# BLL-EBOOK-3506B.net
KiCad netlist of a schematic drawn in EAGLE
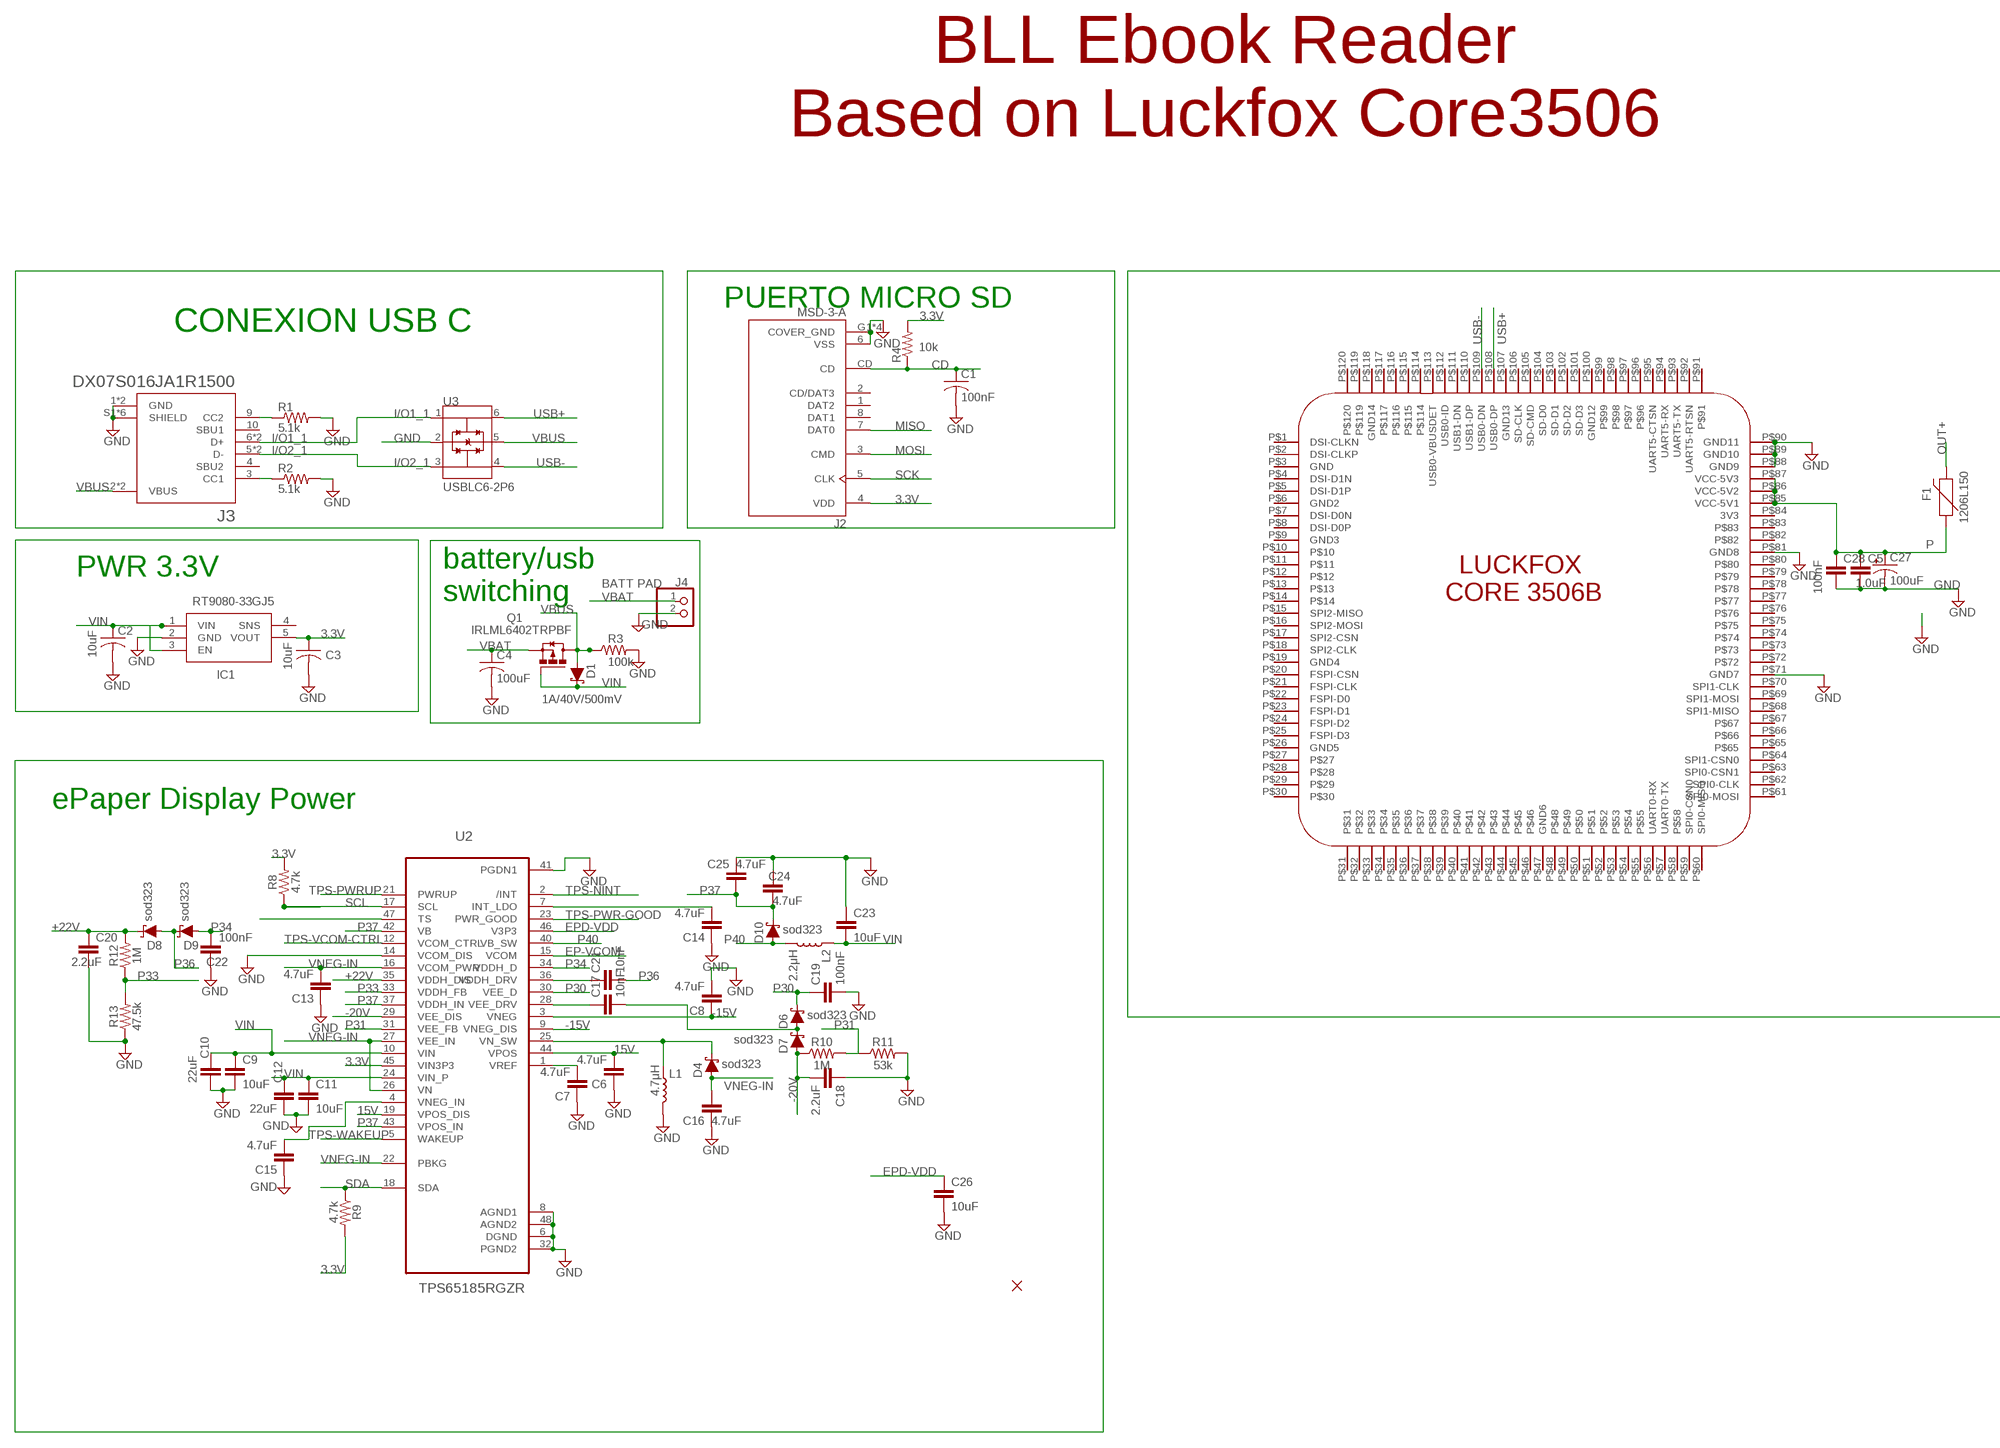
[diagram p0: schematic, sheet 1, part 1 of 2]
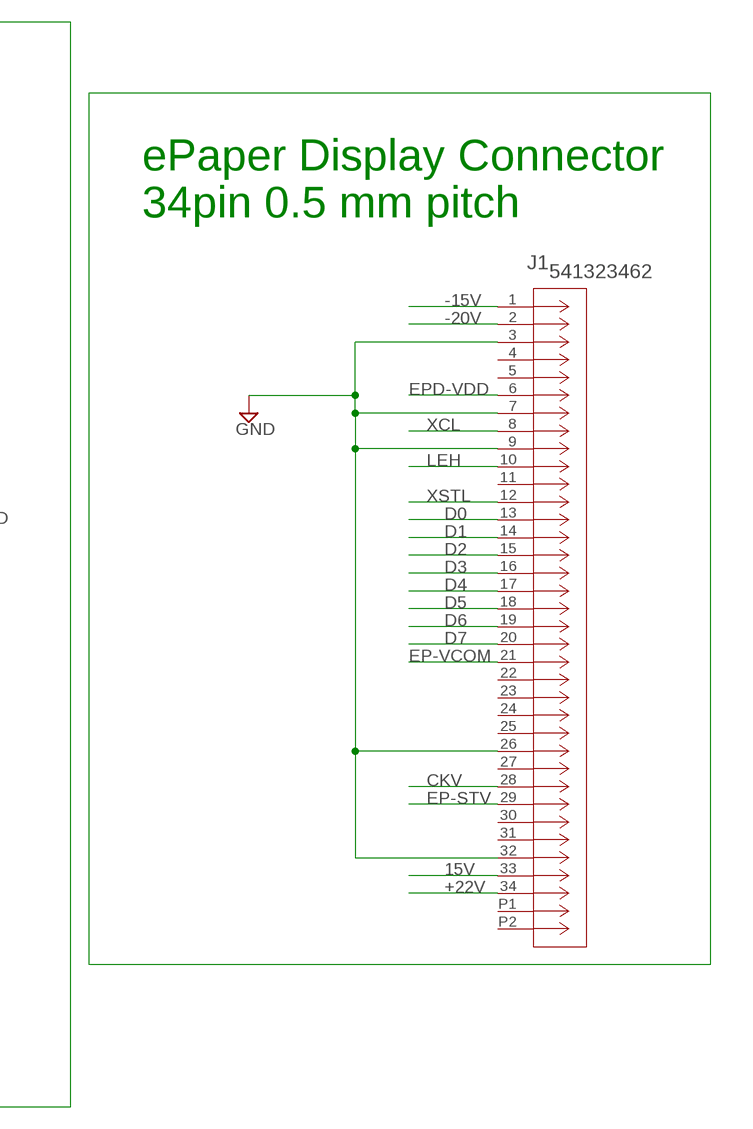
[diagram p1: schematic, sheet 1, part 2 of 2]

(export (version "E")
  (design (tool "Eeschema 10.0.6"))
  (components
    (comp (ref "C1")
      (value "100nF")
      (footprint "eagle-import:C0603")
      (libsource (lib "eagle-import") (part "C-USC0603"))
    )
    (comp (ref "C2")
      (value "10uF")
      (footprint "eagle-import:C0603")
      (libsource (lib "eagle-import") (part "C-USC0603"))
    )
    (comp (ref "C3")
      (value "10uF")
      (footprint "eagle-import:C0603")
      (libsource (lib "eagle-import") (part "C-USC0603"))
    )
    (comp (ref "C4")
      (value "100uF")
      (footprint "eagle-import:C0603")
      (libsource (lib "eagle-import") (part "C-USC0603"))
    )
    (comp (ref "C5")
      (value "1.0uF")
      (footprint "eagle-import:0603")
      (libsource (lib "eagle-import") (part "1.0UF-0603-16V-10%-X7R"))
    )
    (comp (ref "C6")
      (value "4.7uF")
      (footprint "eagle-import:0603")
      (libsource (lib "eagle-import") (part "4.7UF-0603-35V-(20%)"))
    )
    (comp (ref "C7")
      (value "4.7uF")
      (footprint "eagle-import:0603")
      (libsource (lib "eagle-import") (part "4.7UF-0603-35V-(20%)"))
    )
    (comp (ref "C8")
      (value "4.7uF")
      (footprint "eagle-import:0603")
      (libsource (lib "eagle-import") (part "4.7UF-0603-35V-(20%)"))
    )
    (comp (ref "C9")
      (value "10uF")
      (footprint "eagle-import:0805")
      (libsource (lib "eagle-import") (part "10UF-0805-10V-10%"))
    )
    (comp (ref "C10")
      (value "22uF")
      (footprint "eagle-import:0805")
      (libsource (lib "eagle-import") (part "22UF-0805-16V-20%"))
    )
    (comp (ref "C11")
      (value "10uF")
      (footprint "eagle-import:0805")
      (libsource (lib "eagle-import") (part "10UF-0805-10V-10%"))
    )
    (comp (ref "C12")
      (value "22uF")
      (footprint "eagle-import:0805")
      (libsource (lib "eagle-import") (part "22UF-0805-16V-20%"))
    )
    (comp (ref "C13")
      (value "4.7uF")
      (footprint "eagle-import:0603")
      (libsource (lib "eagle-import") (part "4.7UF-0603-35V-(20%)"))
    )
    (comp (ref "C14")
      (value "4.7uF")
      (footprint "eagle-import:0603")
      (libsource (lib "eagle-import") (part "4.7UF-0603-35V-(20%)"))
    )
    (comp (ref "C15")
      (value "4.7uF")
      (footprint "eagle-import:0603")
      (libsource (lib "eagle-import") (part "4.7UF-0603-35V-(20%)"))
    )
    (comp (ref "C16")
      (value "4.7uF")
      (footprint "eagle-import:0603")
      (libsource (lib "eagle-import") (part "4.7UF-0603-35V-(20%)"))
    )
    (comp (ref "C17")
      (value "10nF")
      (footprint "eagle-import:0603")
      (libsource (lib "eagle-import") (part "10NF-0603-50V-10%"))
    )
    (comp (ref "C18")
      (value "2.2uF")
      (footprint "eagle-import:1206")
      (libsource (lib "eagle-import") (part "2.2UF-1206-50V-10%"))
    )
    (comp (ref "C19")
      (value "100nF")
      (footprint "eagle-import:0603")
      (libsource (lib "eagle-import") (part "DNP-0603"))
    )
    (comp (ref "C20")
      (value "2.2uF")
      (footprint "eagle-import:1206")
      (libsource (lib "eagle-import") (part "2.2UF-1206-50V-10%"))
    )
    (comp (ref "C21")
      (value "10nF")
      (footprint "eagle-import:0603")
      (libsource (lib "eagle-import") (part "10NF-0603-50V-10%"))
    )
    (comp (ref "C22")
      (value "100nF")
      (footprint "eagle-import:0603")
      (libsource (lib "eagle-import") (part "DNP-0603"))
    )
    (comp (ref "C23")
      (value "10uF")
      (footprint "eagle-import:0805")
      (libsource (lib "eagle-import") (part "10UF-0805-10V-10%"))
    )
    (comp (ref "C24")
      (value "4.7uF")
      (footprint "eagle-import:0603")
      (libsource (lib "eagle-import") (part "4.7UF-0603-35V-(20%)"))
    )
    (comp (ref "C25")
      (value "4.7uF")
      (footprint "eagle-import:0603")
      (libsource (lib "eagle-import") (part "4.7UF-0603-35V-(20%)"))
    )
    (comp (ref "C26")
      (value "10uF")
      (footprint "eagle-import:0805")
      (libsource (lib "eagle-import") (part "10UF-0805-10V-10%"))
    )
    (comp (ref "C27")
      (value "100uF")
      (footprint "eagle-import:EIA3528")
      (libsource (lib "eagle-import") (part "100UF-POLAR-EIA3528-10V-20%(TANT)"))
    )
    (comp (ref "C28")
      (value "100nF")
      (footprint "eagle-import:0805")
      (libsource (lib "eagle-import") (part "CAP-0805"))
    )
    (comp (ref "D1")
      (value "1A/40V/500mV")
      (footprint "eagle-import:SMA-DIODE")
      (libsource (lib "eagle-import") (part "DIODE-SCHOTTKY-SS14"))
    )
    (comp (ref "D4")
      (value "sod323")
      (footprint "eagle-import:SOD-323")
      (libsource (lib "eagle-import") (part "DIODE-SCHOTTKY-PMEG4005EJ"))
    )
    (comp (ref "D6")
      (value "sod323")
      (footprint "eagle-import:SOD-323")
      (libsource (lib "eagle-import") (part "DIODE-SCHOTTKY-PMEG4005EJ"))
    )
    (comp (ref "D7")
      (value "sod323")
      (footprint "eagle-import:SOD-323")
      (libsource (lib "eagle-import") (part "DIODE-SCHOTTKY-PMEG4005EJ"))
    )
    (comp (ref "D8")
      (value "sod323")
      (footprint "eagle-import:SOD-323")
      (libsource (lib "eagle-import") (part "DIODE-SCHOTTKY-PMEG4005EJ"))
    )
    (comp (ref "D9")
      (value "sod323")
      (footprint "eagle-import:SOD-323")
      (libsource (lib "eagle-import") (part "DIODE-SCHOTTKY-PMEG4005EJ"))
    )
    (comp (ref "D10")
      (value "sod323")
      (footprint "eagle-import:SOD-323")
      (libsource (lib "eagle-import") (part "DIODE-SCHOTTKY-PMEG4005EJ"))
    )
    (comp (ref "F1")
      (value "1206L150")
      (footprint "eagle-import:1206")
      (libsource (lib "eagle-import") (part "PPTC_6V500MA-2"))
    )
    (comp (ref "IC1")
      (value "RT9080-33GJ5")
      (footprint "eagle-import:SOT94P280X100-5N")
      (fields (field (name "MF") "Richtek USA"))
      (libsource (lib "eagle-import") (part "RT9080-33GJ5"))
    )
    (comp (ref "J1")
      (value "541323462")
      (footprint "eagle-import:CON_541323462_MOL")
      (fields (field (name "MF") "Molex"))
      (libsource (lib "eagle-import") (part "541323462"))
    )
    (comp (ref "J2")
      (value "MSD-3-A")
      (footprint "eagle-import:CUI_MSD-3-A")
      (fields (field (name "MF") "Same Sky"))
      (libsource (lib "eagle-import") (part "MSD-3-A"))
    )
    (comp (ref "J3")
      (value "DX07S016JA1R1500")
      (footprint "eagle-import:JAE_DX07S016JA1R1500")
      (fields (field (name "MF") "JAE Electronics"))
      (libsource (lib "eagle-import") (part "DX07S016JA1R1500"))
    )
    (comp (ref "J4")
      (value "BATT PAD")
      (footprint "eagle-import:1X02_90")
      (libsource (lib "eagle-import") (part "PINHD-1X2/90"))
    )
    (comp (ref "L1")
      (value "4.7μH")
      (footprint "eagle-import:1008(2520)")
      (libsource (lib "eagle-import") (part "4.7μH_SHIELDED_INDUCTOR"))
    )
    (comp (ref "L2")
      (value "2.2μH")
      (footprint "eagle-import:0806")
      (libsource (lib "eagle-import") (part "2.2μH_SHIELDED_INDUCTOR"))
    )
    (comp (ref "Q1")
      (value "IRLML6402TRPBF")
      (footprint "eagle-import:SOT23")
      (fields (field (name "MF") "Infineon Technologies") (field (name "MP") "IRLML6402"))
      (libsource (lib "eagle-import") (part "IRLML6402TRPBF"))
    )
    (comp (ref "R1")
      (value "5.1k")
      (footprint "eagle-import:M0805")
      (libsource (lib "eagle-import") (part "R-US_M0805"))
    )
    (comp (ref "R2")
      (value "5.1k")
      (footprint "eagle-import:M0805")
      (libsource (lib "eagle-import") (part "R-US_M0805"))
    )
    (comp (ref "R3")
      (value "100k")
      (footprint "eagle-import:R0603")
      (libsource (lib "eagle-import") (part "R-US_R0603"))
    )
    (comp (ref "R4")
      (value "10k")
      (footprint "eagle-import:M0805")
      (libsource (lib "eagle-import") (part "R-US_M0805"))
    )
    (comp (ref "R8")
      (value "4.7k")
      (footprint "eagle-import:0603")
      (libsource (lib "eagle-import") (part "4.7KOHM-0603-1/10W-1%"))
    )
    (comp (ref "R9")
      (value "4.7k")
      (footprint "eagle-import:0603")
      (libsource (lib "eagle-import") (part "4.7KOHM-0603-1/10W-1%"))
    )
    (comp (ref "R10")
      (value "1M")
      (footprint "eagle-import:0603")
      (libsource (lib "eagle-import") (part "1MOHM-0603-1/4W-5%"))
    )
    (comp (ref "R11")
      (value "53k")
      (footprint "eagle-import:0805")
      (libsource (lib "eagle-import") (part "RESISTOR0805"))
    )
    (comp (ref "R12")
      (value "1M")
      (footprint "eagle-import:0603")
      (libsource (lib "eagle-import") (part "1MOHM-0603-1/4W-5%"))
    )
    (comp (ref "R13")
      (value "47.5k")
      (footprint "eagle-import:0805")
      (libsource (lib "eagle-import") (part "RESISTOR0805"))
    )
    (comp (ref "U$1")
      (value "LUCKFOX_CORE3506")
      (footprint "eagle-import:CORE3506")
      (libsource (lib "eagle-import") (part "LUCKFOX_CORE3506"))
    )
    (comp (ref "U2")
      (value "TPS65185RGZR")
      (footprint "eagle-import:QFN50P700X700X100-49N")
      (fields (field (name "MF") "Texas Instruments"))
      (libsource (lib "eagle-import") (part "TPS65185RGZR"))
    )
    (comp (ref "U3")
      (value "USBLC6-2P6")
      (footprint "eagle-import:SOT50P160X60-6N")
      (fields (field (name "MF") "STMicroelectronics"))
      (libsource (lib "eagle-import") (part "USBLC6-2P6"))
    )
  )
  (nets
    (net (code "1") (name "/+22V") (class "Default")
      (node (ref "C20") (pin "1") (pinfunction "1_1") (pintype "passive"))
      (node (ref "D8") (pin "C") (pinfunction "C_C") (pintype "passive"))
      (node (ref "J1") (pin "34") (pinfunction "34_34") (pintype "passive"))
      (node (ref "R12") (pin "2") (pinfunction "2_2") (pintype "passive"))
      (node (ref "U2") (pin "35") (pinfunction "VDDH_DIS_35") (pintype "input"))
    )
    (net (code "2") (name "/-15V") (class "Default")
      (node (ref "C8") (pin "1") (pinfunction "1_1") (pintype "passive"))
      (node (ref "J1") (pin "1") (pinfunction "1_1") (pintype "passive"))
      (node (ref "U2") (pin "3") (pinfunction "VNEG_3") (pintype "output"))
      (node (ref "U2") (pin "9") (pinfunction "VNEG_DIS_9") (pintype "output"))
    )
    (net (code "3") (name "/-20V") (class "Default")
      (node (ref "C18") (pin "2") (pinfunction "2_2") (pintype "passive"))
      (node (ref "D7") (pin "A") (pinfunction "A_A") (pintype "passive"))
      (node (ref "J1") (pin "2") (pinfunction "2_2") (pintype "passive"))
      (node (ref "R10") (pin "1") (pinfunction "1_1") (pintype "passive"))
      (node (ref "U2") (pin "29") (pinfunction "VEE_DIS_29") (pintype "input"))
    )
    (net (code "4") (name "/3.3V") (class "Default")
      (node (ref "C3") (pin "1") (pinfunction "1_1") (pintype "passive"))
      (node (ref "IC1") (pin "5") (pinfunction "VOUT_5") (pintype "bidirectional"))
      (node (ref "J2") (pin "4") (pinfunction "VDD_4") (pintype "power_in"))
      (node (ref "R4") (pin "2") (pinfunction "2_2") (pintype "passive"))
      (node (ref "R8") (pin "2") (pinfunction "2_2") (pintype "passive"))
      (node (ref "R9") (pin "2") (pinfunction "2_2") (pintype "passive"))
      (node (ref "U2") (pin "45") (pinfunction "VIN3P3_45") (pintype "input"))
    )
    (net (code "5") (name "/15V") (class "Default")
      (node (ref "C6") (pin "2") (pinfunction "2_2") (pintype "passive"))
      (node (ref "J1") (pin "33") (pinfunction "33_33") (pintype "passive"))
      (node (ref "U2") (pin "19") (pinfunction "VPOS_DIS_19") (pintype "input"))
      (node (ref "U2") (pin "44") (pinfunction "VPOS_44") (pintype "output"))
    )
    (net (code "6") (name "/CD") (class "Default")
      (node (ref "C1") (pin "1") (pinfunction "1_1") (pintype "passive"))
      (node (ref "J2") (pin "CD") (pinfunction "CD_CD") (pintype "passive"))
      (node (ref "R4") (pin "1") (pinfunction "1_1") (pintype "passive"))
    )
    (net (code "7") (name "/CKV") (class "Default")
      (node (ref "J1") (pin "28") (pinfunction "28_28") (pintype "passive"))
    )
    (net (code "8") (name "/D0") (class "Default")
      (node (ref "J1") (pin "13") (pinfunction "13_13") (pintype "passive"))
    )
    (net (code "9") (name "/D1") (class "Default")
      (node (ref "J1") (pin "14") (pinfunction "14_14") (pintype "passive"))
    )
    (net (code "10") (name "/D2") (class "Default")
      (node (ref "J1") (pin "15") (pinfunction "15_15") (pintype "passive"))
    )
    (net (code "11") (name "/D3") (class "Default")
      (node (ref "J1") (pin "16") (pinfunction "16_16") (pintype "passive"))
    )
    (net (code "12") (name "/D4") (class "Default")
      (node (ref "J1") (pin "17") (pinfunction "17_17") (pintype "passive"))
    )
    (net (code "13") (name "/D5") (class "Default")
      (node (ref "J1") (pin "18") (pinfunction "18_18") (pintype "passive"))
    )
    (net (code "14") (name "/D6") (class "Default")
      (node (ref "J1") (pin "19") (pinfunction "19_19") (pintype "passive"))
    )
    (net (code "15") (name "/D7") (class "Default")
      (node (ref "J1") (pin "20") (pinfunction "20_20") (pintype "passive"))
    )
    (net (code "16") (name "/EP-STV") (class "Default")
      (node (ref "J1") (pin "29") (pinfunction "29_29") (pintype "passive"))
    )
    (net (code "17") (name "/EP-VCOM") (class "Default")
      (node (ref "J1") (pin "21") (pinfunction "21_21") (pintype "passive"))
      (node (ref "U2") (pin "15") (pinfunction "VCOM_15") (pintype "output"))
    )
    (net (code "18") (name "/EPD-VDD") (class "Default")
      (node (ref "C26") (pin "1") (pinfunction "1_1") (pintype "passive"))
      (node (ref "J1") (pin "6") (pinfunction "6_6") (pintype "passive"))
      (node (ref "U2") (pin "46") (pinfunction "V3P3_46") (pintype "output"))
    )
    (net (code "19") (name "/I{slash}O1_1") (class "Default")
      (node (ref "J3") (pin "6") (pinfunction "D+_6") (pintype "passive"))
      (node (ref "J3") (pin "7") (pinfunction "D+_7") (pintype "passive"))
      (node (ref "U3") (pin "1") (pinfunction "I/O1_1_1") (pintype "bidirectional"))
    )
    (net (code "20") (name "/I{slash}O2_1") (class "Default")
      (node (ref "J3") (pin "5") (pinfunction "D-_5") (pintype "passive"))
      (node (ref "J3") (pin "8") (pinfunction "D-_8") (pintype "passive"))
      (node (ref "U3") (pin "3") (pinfunction "I/O2_1_3") (pintype "bidirectional"))
    )
    (net (code "21") (name "/LEH") (class "Default")
      (node (ref "J1") (pin "10") (pinfunction "10_10") (pintype "passive"))
    )
    (net (code "22") (name "/MISO") (class "Default")
      (node (ref "J2") (pin "7") (pinfunction "DAT0_7") (pintype "bidirectional"))
    )
    (net (code "23") (name "/MOSI") (class "Default")
      (node (ref "J2") (pin "3") (pinfunction "CMD_3") (pintype "bidirectional"))
    )
    (net (code "24") (name "/OUT+") (class "Default")
      (node (ref "F1") (pin "2") (pinfunction "2_2") (pintype "bidirectional"))
    )
    (net (code "25") (name "/P") (class "Default")
      (node (ref "C27") (pin "A") (pinfunction "+_A") (pintype "passive"))
      (node (ref "C28") (pin "1") (pinfunction "1_1") (pintype "passive"))
      (node (ref "C5") (pin "1") (pinfunction "1_1") (pintype "passive"))
      (node (ref "F1") (pin "1") (pinfunction "1_1") (pintype "bidirectional"))
      (node (ref "U$1") (pin "P$85") (pinfunction "VCC-5V1_P$85") (pintype "bidirectional"))
      (node (ref "U$1") (pin "P$86") (pinfunction "VCC-5V2_P$86") (pintype "bidirectional"))
      (node (ref "U$1") (pin "P$87") (pinfunction "VCC-5V3_P$87") (pintype "bidirectional"))
    )
    (net (code "26") (name "/P30") (class "Default")
      (node (ref "C19") (pin "1") (pinfunction "1_1") (pintype "passive"))
      (node (ref "D6") (pin "C") (pinfunction "C_C") (pintype "passive"))
      (node (ref "U2") (pin "30") (pinfunction "VEE_D_30") (pintype "output"))
    )
    (net (code "27") (name "/P31") (class "Default")
      (node (ref "R10") (pin "2") (pinfunction "2_2") (pintype "passive"))
      (node (ref "R11") (pin "1") (pinfunction "1_1") (pintype "passive"))
      (node (ref "U2") (pin "31") (pinfunction "VEE_FB_31") (pintype "input"))
    )
    (net (code "28") (name "/P33") (class "Default")
      (node (ref "R12") (pin "1") (pinfunction "1_1") (pintype "passive"))
      (node (ref "R13") (pin "2") (pinfunction "2_2") (pintype "passive"))
      (node (ref "U2") (pin "33") (pinfunction "VDDH_FB_33") (pintype "input"))
    )
    (net (code "29") (name "/P34") (class "Default")
      (node (ref "C22") (pin "2") (pinfunction "2_2") (pintype "passive"))
      (node (ref "D9") (pin "A") (pinfunction "A_A") (pintype "passive"))
      (node (ref "U2") (pin "34") (pinfunction "VDDH_D_34") (pintype "output"))
    )
    (net (code "30") (name "/P36") (class "Default")
      (node (ref "C21") (pin "2") (pinfunction "2_2") (pintype "passive"))
      (node (ref "D8") (pin "A") (pinfunction "A_A") (pintype "passive"))
      (node (ref "D9") (pin "C") (pinfunction "C_C") (pintype "passive"))
    )
    (net (code "31") (name "/P37") (class "Default")
      (node (ref "C24") (pin "1") (pinfunction "1_1") (pintype "passive"))
      (node (ref "C25") (pin "1") (pinfunction "1_1") (pintype "passive"))
      (node (ref "D10") (pin "C") (pinfunction "C_C") (pintype "passive"))
      (node (ref "U2") (pin "37") (pinfunction "VDDH_IN_37") (pintype "input"))
      (node (ref "U2") (pin "42") (pinfunction "VB_42") (pintype "input"))
      (node (ref "U2") (pin "43") (pinfunction "VPOS_IN_43") (pintype "input"))
    )
    (net (code "32") (name "/P40") (class "Default")
      (node (ref "D10") (pin "A") (pinfunction "A_A") (pintype "passive"))
      (node (ref "L2") (pin "2") (pinfunction "2_2") (pintype "passive"))
      (node (ref "U2") (pin "40") (pinfunction "VB_SW_40") (pintype "output"))
    )
    (net (code "33") (name "/SCK") (class "Default")
      (node (ref "J2") (pin "5") (pinfunction "CLK_5") (pintype "input"))
    )
    (net (code "34") (name "/SCL") (class "Default")
      (node (ref "R8") (pin "1") (pinfunction "1_1") (pintype "passive"))
      (node (ref "U2") (pin "17") (pinfunction "SCL_17") (pintype "input"))
    )
    (net (code "35") (name "/SDA") (class "Default")
      (node (ref "R9") (pin "1") (pinfunction "1_1") (pintype "passive"))
      (node (ref "U2") (pin "18") (pinfunction "SDA_18") (pintype "bidirectional"))
    )
    (net (code "36") (name "/TPS-NINT") (class "Default")
      (node (ref "U2") (pin "2") (pinfunction "/INT_2") (pintype "output"))
    )
    (net (code "37") (name "/TPS-PWR-GOOD") (class "Default")
      (node (ref "U2") (pin "23") (pinfunction "PWR_GOOD_23") (pintype "output"))
    )
    (net (code "38") (name "/TPS-PWRUP") (class "Default")
      (node (ref "U2") (pin "21") (pinfunction "PWRUP_21") (pintype "input"))
    )
    (net (code "39") (name "/TPS-VCOM-CTRL") (class "Default")
      (node (ref "U2") (pin "12") (pinfunction "VCOM_CTRL_12") (pintype "input"))
    )
    (net (code "40") (name "/TPS-WAKEUP") (class "Default")
      (node (ref "U2") (pin "5") (pinfunction "WAKEUP_5") (pintype "input"))
    )
    (net (code "41") (name "/USB+") (class "Default")
      (node (ref "U$1") (pin "P$108") (pinfunction "USB0-DP_P$108") (pintype "bidirectional"))
      (node (ref "U3") (pin "6") (pinfunction "I/O1_2_6") (pintype "bidirectional"))
    )
    (net (code "42") (name "/USB-") (class "Default")
      (node (ref "U$1") (pin "P$109") (pinfunction "USB0-DN_P$109") (pintype "bidirectional"))
      (node (ref "U3") (pin "4") (pinfunction "I/O2_2_4") (pintype "bidirectional"))
    )
    (net (code "43") (name "/VBAT") (class "Default")
      (node (ref "C4") (pin "1") (pinfunction "1_1") (pintype "passive"))
      (node (ref "J4") (pin "1") (pinfunction "1_1") (pintype "passive"))
      (node (ref "Q1") (pin "2") (pinfunction "S_2") (pintype "passive"))
    )
    (net (code "44") (name "/VBUS") (class "Default")
      (node (ref "D1") (pin "A") (pinfunction "A_A") (pintype "passive"))
      (node (ref "J3") (pin "11") (pinfunction "VBUS_11") (pintype "power_in"))
      (node (ref "J3") (pin "2") (pinfunction "VBUS_2") (pintype "power_in"))
      (node (ref "Q1") (pin "3") (pinfunction "D_3") (pintype "passive"))
      (node (ref "R3") (pin "1") (pinfunction "1_1") (pintype "passive"))
      (node (ref "U3") (pin "5") (pinfunction "VBUS_5") (pintype "power_in"))
    )
    (net (code "45") (name "/VIN") (class "Default")
      (node (ref "C10") (pin "1") (pinfunction "1_1") (pintype "passive"))
      (node (ref "C11") (pin "1") (pinfunction "1_1") (pintype "passive"))
      (node (ref "C12") (pin "1") (pinfunction "1_1") (pintype "passive"))
      (node (ref "C2") (pin "1") (pinfunction "1_1") (pintype "passive"))
      (node (ref "C23") (pin "2") (pinfunction "2_2") (pintype "passive"))
      (node (ref "C9") (pin "1") (pinfunction "1_1") (pintype "passive"))
      (node (ref "D1") (pin "C") (pinfunction "C_C") (pintype "passive"))
      (node (ref "IC1") (pin "1") (pinfunction "VIN_1") (pintype "bidirectional"))
      (node (ref "IC1") (pin "3") (pinfunction "EN_3") (pintype "bidirectional"))
      (node (ref "L2") (pin "1") (pinfunction "1_1") (pintype "passive"))
      (node (ref "Q1") (pin "1") (pinfunction "G_1") (pintype "passive"))
      (node (ref "U2") (pin "10") (pinfunction "VIN_10") (pintype "input"))
      (node (ref "U2") (pin "24") (pinfunction "VIN_P_24") (pintype "input"))
    )
    (net (code "46") (name "/VNEG-IN") (class "Default")
      (node (ref "C13") (pin "2") (pinfunction "2_2") (pintype "passive"))
      (node (ref "C16") (pin "2") (pinfunction "2_2") (pintype "passive"))
      (node (ref "D4") (pin "A") (pinfunction "A_A") (pintype "passive"))
      (node (ref "U2") (pin "16") (pinfunction "VCOM_PWR_16") (pintype "input"))
      (node (ref "U2") (pin "22") (pinfunction "PBKG_22") (pintype "bidirectional"))
      (node (ref "U2") (pin "26") (pinfunction "VN_26") (pintype "input"))
      (node (ref "U2") (pin "27") (pinfunction "VEE_IN_27") (pintype "input"))
    )
    (net (code "47") (name "/XCL") (class "Default")
      (node (ref "J1") (pin "8") (pinfunction "8_8") (pintype "passive"))
    )
    (net (code "48") (name "/XSTL") (class "Default")
      (node (ref "J1") (pin "12") (pinfunction "12_12") (pintype "passive"))
    )
    (net (code "49") (name "GND") (class "Default")
      (node (ref "C1") (pin "2") (pinfunction "2_2") (pintype "passive"))
      (node (ref "C10") (pin "2") (pinfunction "2_2") (pintype "passive"))
      (node (ref "C11") (pin "2") (pinfunction "2_2") (pintype "passive"))
      (node (ref "C12") (pin "2") (pinfunction "2_2") (pintype "passive"))
      (node (ref "C13") (pin "1") (pinfunction "1_1") (pintype "passive"))
      (node (ref "C14") (pin "1") (pinfunction "1_1") (pintype "passive"))
      (node (ref "C15") (pin "1") (pinfunction "1_1") (pintype "passive"))
      (node (ref "C16") (pin "1") (pinfunction "1_1") (pintype "passive"))
      (node (ref "C18") (pin "1") (pinfunction "1_1") (pintype "passive"))
      (node (ref "C19") (pin "2") (pinfunction "2_2") (pintype "passive"))
      (node (ref "C2") (pin "2") (pinfunction "2_2") (pintype "passive"))
      (node (ref "C20") (pin "2") (pinfunction "2_2") (pintype "passive"))
      (node (ref "C22") (pin "1") (pinfunction "1_1") (pintype "passive"))
      (node (ref "C23") (pin "1") (pinfunction "1_1") (pintype "passive"))
      (node (ref "C24") (pin "2") (pinfunction "2_2") (pintype "passive"))
      (node (ref "C25") (pin "2") (pinfunction "2_2") (pintype "passive"))
      (node (ref "C26") (pin "2") (pinfunction "2_2") (pintype "passive"))
      (node (ref "C27") (pin "C") (pinfunction "-_C") (pintype "passive"))
      (node (ref "C28") (pin "2") (pinfunction "2_2") (pintype "passive"))
      (node (ref "C3") (pin "2") (pinfunction "2_2") (pintype "passive"))
      (node (ref "C4") (pin "2") (pinfunction "2_2") (pintype "passive"))
      (node (ref "C5") (pin "2") (pinfunction "2_2") (pintype "passive"))
      (node (ref "C6") (pin "1") (pinfunction "1_1") (pintype "passive"))
      (node (ref "C7") (pin "1") (pinfunction "1_1") (pintype "passive"))
      (node (ref "C8") (pin "2") (pinfunction "2_2") (pintype "passive"))
      (node (ref "C9") (pin "2") (pinfunction "2_2") (pintype "passive"))
      (node (ref "IC1") (pin "2") (pinfunction "GND_2") (pintype "bidirectional"))
      (node (ref "J1") (pin "26") (pinfunction "26_26") (pintype "passive"))
      (node (ref "J1") (pin "3") (pinfunction "3_3") (pintype "passive"))
      (node (ref "J1") (pin "32") (pinfunction "32_32") (pintype "passive"))
      (node (ref "J1") (pin "7") (pinfunction "7_7") (pintype "passive"))
      (node (ref "J1") (pin "9") (pinfunction "9_9") (pintype "passive"))
      (node (ref "J2") (pin "6") (pinfunction "VSS_6") (pintype "power_in"))
      (node (ref "J2") (pin "G1") (pinfunction "COVER_GND_G1") (pintype "power_in"))
      (node (ref "J2") (pin "G2") (pinfunction "COVER_GND_G2") (pintype "power_in"))
      (node (ref "J2") (pin "G3") (pinfunction "COVER_GND_G3") (pintype "power_in"))
      (node (ref "J2") (pin "G4") (pinfunction "COVER_GND_G4") (pintype "power_in"))
      (node (ref "J3") (pin "1") (pinfunction "GND_1") (pintype "power_in"))
      (node (ref "J3") (pin "12") (pinfunction "GND_12") (pintype "power_in"))
      (node (ref "J3") (pin "S1") (pinfunction "SHIELD_S1") (pintype "passive"))
      (node (ref "J3") (pin "S2") (pinfunction "SHIELD_S2") (pintype "passive"))
      (node (ref "J3") (pin "S3") (pinfunction "SHIELD_S3") (pintype "passive"))
      (node (ref "J3") (pin "S4") (pinfunction "SHIELD_S4") (pintype "passive"))
      (node (ref "J3") (pin "S5") (pinfunction "SHIELD_S5") (pintype "passive"))
      (node (ref "J3") (pin "S6") (pinfunction "SHIELD_S6") (pintype "passive"))
      (node (ref "J4") (pin "2") (pinfunction "2_2") (pintype "passive"))
      (node (ref "L1") (pin "2") (pinfunction "2_2") (pintype "passive"))
      (node (ref "R1") (pin "2") (pinfunction "2_2") (pintype "passive"))
      (node (ref "R11") (pin "2") (pinfunction "2_2") (pintype "passive"))
      (node (ref "R13") (pin "1") (pinfunction "1_1") (pintype "passive"))
      (node (ref "R2") (pin "2") (pinfunction "2_2") (pintype "passive"))
      (node (ref "R3") (pin "2") (pinfunction "2_2") (pintype "passive"))
      (node (ref "U$1") (pin "P$71") (pinfunction "GND7_P$71") (pintype "bidirectional"))
      (node (ref "U$1") (pin "P$81") (pinfunction "GND8_P$81") (pintype "bidirectional"))
      (node (ref "U$1") (pin "P$88") (pinfunction "GND9_P$88") (pintype "bidirectional"))
      (node (ref "U$1") (pin "P$89") (pinfunction "GND10_P$89") (pintype "bidirectional"))
      (node (ref "U$1") (pin "P$90") (pinfunction "GND11_P$90") (pintype "bidirectional"))
      (node (ref "U2") (pin "14") (pinfunction "VCOM_DIS_14") (pintype "input"))
      (node (ref "U2") (pin "32") (pinfunction "PGND2_32") (pintype "power_in"))
      (node (ref "U2") (pin "41") (pinfunction "PGDN1_41") (pintype "power_in"))
      (node (ref "U2") (pin "48") (pinfunction "AGND2_48") (pintype "power_in"))
      (node (ref "U2") (pin "6") (pinfunction "DGND_6") (pintype "power_in"))
      (node (ref "U2") (pin "8") (pinfunction "AGND1_8") (pintype "power_in"))
      (node (ref "U3") (pin "2") (pinfunction "GND_2") (pintype "power_in"))
    )
    (net (code "50") (name "Net-(C17-Pad2)") (class "Default")
      (node (ref "C17") (pin "2") (pinfunction "2_2") (pintype "passive"))
      (node (ref "D6") (pin "A") (pinfunction "A_A") (pintype "passive"))
      (node (ref "D7") (pin "C") (pinfunction "C_C") (pintype "passive"))
    )
    (net (code "51") (name "Net-(J3-CC1)") (class "Default")
      (node (ref "J3") (pin "3") (pinfunction "CC1_3") (pintype "passive"))
      (node (ref "R2") (pin "1") (pinfunction "1_1") (pintype "passive"))
    )
    (net (code "52") (name "Net-(J3-CC2)") (class "Default")
      (node (ref "J3") (pin "9") (pinfunction "CC2_9") (pintype "passive"))
      (node (ref "R1") (pin "1") (pinfunction "1_1") (pintype "passive"))
    )
    (net (code "53") (name "Net-(U2-INT_LDO)") (class "Default")
      (node (ref "C14") (pin "2") (pinfunction "2_2") (pintype "passive"))
      (node (ref "U2") (pin "7") (pinfunction "INT_LDO_7") (pintype "output"))
    )
    (net (code "54") (name "Net-(U2-VDDH_DRV)") (class "Default")
      (node (ref "C21") (pin "1") (pinfunction "1_1") (pintype "passive"))
      (node (ref "U2") (pin "36") (pinfunction "VDDH_DRV_36") (pintype "output"))
    )
    (net (code "55") (name "Net-(U2-VEE_DRV)") (class "Default")
      (node (ref "C17") (pin "1") (pinfunction "1_1") (pintype "passive"))
      (node (ref "U2") (pin "28") (pinfunction "VEE_DRV_28") (pintype "output"))
    )
    (net (code "56") (name "Net-(U2-VNEG_IN)") (class "Default")
      (node (ref "C15") (pin "2") (pinfunction "2_2") (pintype "passive"))
      (node (ref "U2") (pin "4") (pinfunction "VNEG_IN_4") (pintype "input"))
    )
    (net (code "57") (name "Net-(U2-VN_SW)") (class "Default")
      (node (ref "D4") (pin "C") (pinfunction "C_C") (pintype "passive"))
      (node (ref "L1") (pin "1") (pinfunction "1_1") (pintype "passive"))
      (node (ref "U2") (pin "25") (pinfunction "VN_SW_25") (pintype "output"))
    )
    (net (code "58") (name "Net-(U2-VREF)") (class "Default")
      (node (ref "C7") (pin "2") (pinfunction "2_2") (pintype "passive"))
      (node (ref "U2") (pin "1") (pinfunction "VREF_1") (pintype "output"))
    )
    (net (code "59") (name "unconnected-(IC1-SNS-Pad4)") (class "Default")
      (node (ref "IC1") (pin "4") (pinfunction "SNS_4") (pintype "bidirectional"))
    )
    (net (code "60") (name "unconnected-(J1-Pad4)") (class "Default")
      (node (ref "J1") (pin "4") (pinfunction "4_4") (pintype "passive"))
    )
    (net (code "61") (name "unconnected-(J1-Pad5)") (class "Default")
      (node (ref "J1") (pin "5") (pinfunction "5_5") (pintype "passive"))
    )
    (net (code "62") (name "unconnected-(J1-Pad11)") (class "Default")
      (node (ref "J1") (pin "11") (pinfunction "11_11") (pintype "passive"))
    )
    (net (code "63") (name "unconnected-(J1-Pad22)") (class "Default")
      (node (ref "J1") (pin "22") (pinfunction "22_22") (pintype "passive"))
    )
    (net (code "64") (name "unconnected-(J1-Pad23)") (class "Default")
      (node (ref "J1") (pin "23") (pinfunction "23_23") (pintype "passive"))
    )
    (net (code "65") (name "unconnected-(J1-Pad24)") (class "Default")
      (node (ref "J1") (pin "24") (pinfunction "24_24") (pintype "passive"))
    )
    (net (code "66") (name "unconnected-(J1-Pad25)") (class "Default")
      (node (ref "J1") (pin "25") (pinfunction "25_25") (pintype "passive"))
    )
    (net (code "67") (name "unconnected-(J1-Pad27)") (class "Default")
      (node (ref "J1") (pin "27") (pinfunction "27_27") (pintype "passive"))
    )
    (net (code "68") (name "unconnected-(J1-Pad30)") (class "Default")
      (node (ref "J1") (pin "30") (pinfunction "30_30") (pintype "passive"))
    )
    (net (code "69") (name "unconnected-(J1-Pad31)") (class "Default")
      (node (ref "J1") (pin "31") (pinfunction "31_31") (pintype "passive"))
    )
    (net (code "70") (name "unconnected-(J1-PadP1)") (class "Default")
      (node (ref "J1") (pin "P1") (pinfunction "P1_P1") (pintype "passive"))
    )
    (net (code "71") (name "unconnected-(J1-PadP2)") (class "Default")
      (node (ref "J1") (pin "P2") (pinfunction "P2_P2") (pintype "passive"))
    )
    (net (code "72") (name "unconnected-(J2-CD{slash}DAT3-Pad2)") (class "Default")
      (node (ref "J2") (pin "2") (pinfunction "CD/DAT3_2") (pintype "bidirectional"))
    )
    (net (code "73") (name "unconnected-(J2-DAT1-Pad8)") (class "Default")
      (node (ref "J2") (pin "8") (pinfunction "DAT1_8") (pintype "bidirectional"))
    )
    (net (code "74") (name "unconnected-(J2-DAT2-Pad1)") (class "Default")
      (node (ref "J2") (pin "1") (pinfunction "DAT2_1") (pintype "bidirectional"))
    )
    (net (code "75") (name "unconnected-(J3-SBU1-Pad10)") (class "Default")
      (node (ref "J3") (pin "10") (pinfunction "SBU1_10") (pintype "passive"))
    )
    (net (code "76") (name "unconnected-(J3-SBU2-Pad4)") (class "Default")
      (node (ref "J3") (pin "4") (pinfunction "SBU2_4") (pintype "passive"))
    )
    (net (code "77") (name "unconnected-(U$1-3V3-PadP$84)") (class "Default")
      (node (ref "U$1") (pin "P$84") (pinfunction "3V3_P$84") (pintype "bidirectional"))
    )
    (net (code "78") (name "unconnected-(U$1-DSI-CLKN-PadP$1)") (class "Default")
      (node (ref "U$1") (pin "P$1") (pinfunction "DSI-CLKN_P$1") (pintype "output"))
    )
    (net (code "79") (name "unconnected-(U$1-DSI-CLKP-PadP$2)") (class "Default")
      (node (ref "U$1") (pin "P$2") (pinfunction "DSI-CLKP_P$2") (pintype "bidirectional"))
    )
    (net (code "80") (name "unconnected-(U$1-DSI-D0N-PadP$7)") (class "Default")
      (node (ref "U$1") (pin "P$7") (pinfunction "DSI-D0N_P$7") (pintype "bidirectional"))
    )
    (net (code "81") (name "unconnected-(U$1-DSI-D0P-PadP$8)") (class "Default")
      (node (ref "U$1") (pin "P$8") (pinfunction "DSI-D0P_P$8") (pintype "bidirectional"))
    )
    (net (code "82") (name "unconnected-(U$1-DSI-D1N-PadP$4)") (class "Default")
      (node (ref "U$1") (pin "P$4") (pinfunction "DSI-D1N_P$4") (pintype "bidirectional"))
    )
    (net (code "83") (name "unconnected-(U$1-DSI-D1P-PadP$5)") (class "Default")
      (node (ref "U$1") (pin "P$5") (pinfunction "DSI-D1P_P$5") (pintype "bidirectional"))
    )
    (net (code "84") (name "unconnected-(U$1-FSPI-CLK-PadP$21)") (class "Default")
      (node (ref "U$1") (pin "P$21") (pinfunction "FSPI-CLK_P$21") (pintype "bidirectional"))
    )
    (net (code "85") (name "unconnected-(U$1-FSPI-CSN-PadP$20)") (class "Default")
      (node (ref "U$1") (pin "P$20") (pinfunction "FSPI-CSN_P$20") (pintype "bidirectional"))
    )
    (net (code "86") (name "unconnected-(U$1-FSPI-D0-PadP$22)") (class "Default")
      (node (ref "U$1") (pin "P$22") (pinfunction "FSPI-D0_P$22") (pintype "bidirectional"))
    )
    (net (code "87") (name "unconnected-(U$1-FSPI-D1-PadP$23)") (class "Default")
      (node (ref "U$1") (pin "P$23") (pinfunction "FSPI-D1_P$23") (pintype "bidirectional"))
    )
    (net (code "88") (name "unconnected-(U$1-FSPI-D2-PadP$24)") (class "Default")
      (node (ref "U$1") (pin "P$24") (pinfunction "FSPI-D2_P$24") (pintype "bidirectional"))
    )
    (net (code "89") (name "unconnected-(U$1-FSPI-D3-PadP$25)") (class "Default")
      (node (ref "U$1") (pin "P$25") (pinfunction "FSPI-D3_P$25") (pintype "bidirectional"))
    )
    (net (code "90") (name "unconnected-(U$1-GND-PadP$3)") (class "Default")
      (node (ref "U$1") (pin "P$3") (pinfunction "GND_P$3") (pintype "bidirectional"))
    )
    (net (code "91") (name "unconnected-(U$1-GND2-PadP$6)") (class "Default")
      (node (ref "U$1") (pin "P$6") (pinfunction "GND2_P$6") (pintype "bidirectional"))
    )
    (net (code "92") (name "unconnected-(U$1-GND3-PadP$9)") (class "Default")
      (node (ref "U$1") (pin "P$9") (pinfunction "GND3_P$9") (pintype "bidirectional"))
    )
    (net (code "93") (name "unconnected-(U$1-GND4-PadP$19)") (class "Default")
      (node (ref "U$1") (pin "P$19") (pinfunction "GND4_P$19") (pintype "bidirectional"))
    )
    (net (code "94") (name "unconnected-(U$1-GND5-PadP$26)") (class "Default")
      (node (ref "U$1") (pin "P$26") (pinfunction "GND5_P$26") (pintype "bidirectional"))
    )
    (net (code "95") (name "unconnected-(U$1-GND6-PadP$47)") (class "Default")
      (node (ref "U$1") (pin "P$47") (pinfunction "GND6_P$47") (pintype "bidirectional"))
    )
    (net (code "96") (name "unconnected-(U$1-GND12-PadP$100)") (class "Default")
      (node (ref "U$1") (pin "P$100") (pinfunction "GND12_P$100") (pintype "bidirectional"))
    )
    (net (code "97") (name "unconnected-(U$1-GND13-PadP$107)") (class "Default")
      (node (ref "U$1") (pin "P$107") (pinfunction "GND13_P$107") (pintype "bidirectional"))
    )
    (net (code "98") (name "unconnected-(U$1-GND14-PadP$118)") (class "Default")
      (node (ref "U$1") (pin "P$118") (pinfunction "GND14_P$118") (pintype "bidirectional"))
    )
    (net (code "99") (name "unconnected-(U$1-PadP$10)") (class "Default")
      (node (ref "U$1") (pin "P$10") (pinfunction "P$10_P$10") (pintype "bidirectional"))
    )
    (net (code "100") (name "unconnected-(U$1-PadP$11)") (class "Default")
      (node (ref "U$1") (pin "P$11") (pinfunction "P$11_P$11") (pintype "bidirectional"))
    )
    (net (code "101") (name "unconnected-(U$1-PadP$12)") (class "Default")
      (node (ref "U$1") (pin "P$12") (pinfunction "P$12_P$12") (pintype "bidirectional"))
    )
    (net (code "102") (name "unconnected-(U$1-PadP$13)") (class "Default")
      (node (ref "U$1") (pin "P$13") (pinfunction "P$13_P$13") (pintype "bidirectional"))
    )
    (net (code "103") (name "unconnected-(U$1-PadP$14)") (class "Default")
      (node (ref "U$1") (pin "P$14") (pinfunction "P$14_P$14") (pintype "bidirectional"))
    )
    (net (code "104") (name "unconnected-(U$1-PadP$27)") (class "Default")
      (node (ref "U$1") (pin "P$27") (pinfunction "P$27_P$27") (pintype "bidirectional"))
    )
    (net (code "105") (name "unconnected-(U$1-PadP$28)") (class "Default")
      (node (ref "U$1") (pin "P$28") (pinfunction "P$28_P$28") (pintype "bidirectional"))
    )
    (net (code "106") (name "unconnected-(U$1-PadP$29)") (class "Default")
      (node (ref "U$1") (pin "P$29") (pinfunction "P$29_P$29") (pintype "bidirectional"))
    )
    (net (code "107") (name "unconnected-(U$1-PadP$30)") (class "Default")
      (node (ref "U$1") (pin "P$30") (pinfunction "P$30_P$30") (pintype "bidirectional"))
    )
    (net (code "108") (name "unconnected-(U$1-PadP$31)") (class "Default")
      (node (ref "U$1") (pin "P$31") (pinfunction "P$31_P$31") (pintype "bidirectional"))
    )
    (net (code "109") (name "unconnected-(U$1-PadP$32)") (class "Default")
      (node (ref "U$1") (pin "P$32") (pinfunction "P$32_P$32") (pintype "bidirectional"))
    )
    (net (code "110") (name "unconnected-(U$1-PadP$33)") (class "Default")
      (node (ref "U$1") (pin "P$33") (pinfunction "P$33_P$33") (pintype "bidirectional"))
    )
    (net (code "111") (name "unconnected-(U$1-PadP$34)") (class "Default")
      (node (ref "U$1") (pin "P$34") (pinfunction "P$34_P$34") (pintype "bidirectional"))
    )
    (net (code "112") (name "unconnected-(U$1-PadP$35)") (class "Default")
      (node (ref "U$1") (pin "P$35") (pinfunction "P$35_P$35") (pintype "bidirectional"))
    )
    (net (code "113") (name "unconnected-(U$1-PadP$36)") (class "Default")
      (node (ref "U$1") (pin "P$36") (pinfunction "P$36_P$36") (pintype "bidirectional"))
    )
    (net (code "114") (name "unconnected-(U$1-PadP$37)") (class "Default")
      (node (ref "U$1") (pin "P$37") (pinfunction "P$37_P$37") (pintype "bidirectional"))
    )
    (net (code "115") (name "unconnected-(U$1-PadP$38)") (class "Default")
      (node (ref "U$1") (pin "P$38") (pinfunction "P$38_P$38") (pintype "bidirectional"))
    )
    (net (code "116") (name "unconnected-(U$1-PadP$39)") (class "Default")
      (node (ref "U$1") (pin "P$39") (pinfunction "P$39_P$39") (pintype "bidirectional"))
    )
    (net (code "117") (name "unconnected-(U$1-PadP$40)") (class "Default")
      (node (ref "U$1") (pin "P$40") (pinfunction "P$40_P$40") (pintype "bidirectional"))
    )
    (net (code "118") (name "unconnected-(U$1-PadP$41)") (class "Default")
      (node (ref "U$1") (pin "P$41") (pinfunction "P$41_P$41") (pintype "bidirectional"))
    )
    (net (code "119") (name "unconnected-(U$1-PadP$42)") (class "Default")
      (node (ref "U$1") (pin "P$42") (pinfunction "P$42_P$42") (pintype "bidirectional"))
    )
    (net (code "120") (name "unconnected-(U$1-PadP$43)") (class "Default")
      (node (ref "U$1") (pin "P$43") (pinfunction "P$43_P$43") (pintype "bidirectional"))
    )
    (net (code "121") (name "unconnected-(U$1-PadP$44)") (class "Default")
      (node (ref "U$1") (pin "P$44") (pinfunction "P$44_P$44") (pintype "bidirectional"))
    )
    (net (code "122") (name "unconnected-(U$1-PadP$45)") (class "Default")
      (node (ref "U$1") (pin "P$45") (pinfunction "P$45_P$45") (pintype "bidirectional"))
    )
    (net (code "123") (name "unconnected-(U$1-PadP$46)") (class "Default")
      (node (ref "U$1") (pin "P$46") (pinfunction "P$46_P$46") (pintype "bidirectional"))
    )
    (net (code "124") (name "unconnected-(U$1-PadP$48)") (class "Default")
      (node (ref "U$1") (pin "P$48") (pinfunction "P$48_P$48") (pintype "bidirectional"))
    )
    (net (code "125") (name "unconnected-(U$1-PadP$49)") (class "Default")
      (node (ref "U$1") (pin "P$49") (pinfunction "P$49_P$49") (pintype "bidirectional"))
    )
    (net (code "126") (name "unconnected-(U$1-PadP$50)") (class "Default")
      (node (ref "U$1") (pin "P$50") (pinfunction "P$50_P$50") (pintype "bidirectional"))
    )
    (net (code "127") (name "unconnected-(U$1-PadP$51)") (class "Default")
      (node (ref "U$1") (pin "P$51") (pinfunction "P$51_P$51") (pintype "bidirectional"))
    )
    (net (code "128") (name "unconnected-(U$1-PadP$52)") (class "Default")
      (node (ref "U$1") (pin "P$52") (pinfunction "P$52_P$52") (pintype "bidirectional"))
    )
    (net (code "129") (name "unconnected-(U$1-PadP$53)") (class "Default")
      (node (ref "U$1") (pin "P$53") (pinfunction "P$53_P$53") (pintype "bidirectional"))
    )
    (net (code "130") (name "unconnected-(U$1-PadP$54)") (class "Default")
      (node (ref "U$1") (pin "P$54") (pinfunction "P$54_P$54") (pintype "bidirectional"))
    )
    (net (code "131") (name "unconnected-(U$1-PadP$55)") (class "Default")
      (node (ref "U$1") (pin "P$55") (pinfunction "P$55_P$55") (pintype "bidirectional"))
    )
    (net (code "132") (name "unconnected-(U$1-PadP$58)") (class "Default")
      (node (ref "U$1") (pin "P$58") (pinfunction "P$58_P$58") (pintype "bidirectional"))
    )
    (net (code "133") (name "unconnected-(U$1-PadP$65)") (class "Default")
      (node (ref "U$1") (pin "P$65") (pinfunction "P$65_P$65") (pintype "bidirectional"))
    )
    (net (code "134") (name "unconnected-(U$1-PadP$66)") (class "Default")
      (node (ref "U$1") (pin "P$66") (pinfunction "P$66_P$66") (pintype "bidirectional"))
    )
    (net (code "135") (name "unconnected-(U$1-PadP$67)") (class "Default")
      (node (ref "U$1") (pin "P$67") (pinfunction "P$67_P$67") (pintype "bidirectional"))
    )
    (net (code "136") (name "unconnected-(U$1-PadP$72)") (class "Default")
      (node (ref "U$1") (pin "P$72") (pinfunction "P$72_P$72") (pintype "bidirectional"))
    )
    (net (code "137") (name "unconnected-(U$1-PadP$73)") (class "Default")
      (node (ref "U$1") (pin "P$73") (pinfunction "P$73_P$73") (pintype "bidirectional"))
    )
    (net (code "138") (name "unconnected-(U$1-PadP$74)") (class "Default")
      (node (ref "U$1") (pin "P$74") (pinfunction "P$74_P$74") (pintype "bidirectional"))
    )
    (net (code "139") (name "unconnected-(U$1-PadP$75)") (class "Default")
      (node (ref "U$1") (pin "P$75") (pinfunction "P$75_P$75") (pintype "bidirectional"))
    )
    (net (code "140") (name "unconnected-(U$1-PadP$76)") (class "Default")
      (node (ref "U$1") (pin "P$76") (pinfunction "P$76_P$76") (pintype "bidirectional"))
    )
    (net (code "141") (name "unconnected-(U$1-PadP$77)") (class "Default")
      (node (ref "U$1") (pin "P$77") (pinfunction "P$77_P$77") (pintype "bidirectional"))
    )
    (net (code "142") (name "unconnected-(U$1-PadP$78)") (class "Default")
      (node (ref "U$1") (pin "P$78") (pinfunction "P$78_P$78") (pintype "bidirectional"))
    )
    (net (code "143") (name "unconnected-(U$1-PadP$79)") (class "Default")
      (node (ref "U$1") (pin "P$79") (pinfunction "P$79_P$79") (pintype "bidirectional"))
    )
    (net (code "144") (name "unconnected-(U$1-PadP$80)") (class "Default")
      (node (ref "U$1") (pin "P$80") (pinfunction "P$80_P$80") (pintype "bidirectional"))
    )
    (net (code "145") (name "unconnected-(U$1-PadP$82)") (class "Default")
      (node (ref "U$1") (pin "P$82") (pinfunction "P$82_P$82") (pintype "bidirectional"))
    )
    (net (code "146") (name "unconnected-(U$1-PadP$83)") (class "Default")
      (node (ref "U$1") (pin "P$83") (pinfunction "P$83_P$83") (pintype "bidirectional"))
    )
    (net (code "147") (name "unconnected-(U$1-PadP$91)") (class "Default")
      (node (ref "U$1") (pin "P$91") (pinfunction "P$91_P$91") (pintype "bidirectional"))
    )
    (net (code "148") (name "unconnected-(U$1-PadP$96)") (class "Default")
      (node (ref "U$1") (pin "P$96") (pinfunction "P$96_P$96") (pintype "bidirectional"))
    )
    (net (code "149") (name "unconnected-(U$1-PadP$97)") (class "Default")
      (node (ref "U$1") (pin "P$97") (pinfunction "P$97_P$97") (pintype "bidirectional"))
    )
    (net (code "150") (name "unconnected-(U$1-PadP$98)") (class "Default")
      (node (ref "U$1") (pin "P$98") (pinfunction "P$98_P$98") (pintype "bidirectional"))
    )
    (net (code "151") (name "unconnected-(U$1-PadP$99)") (class "Default")
      (node (ref "U$1") (pin "P$99") (pinfunction "P$99_P$99") (pintype "bidirectional"))
    )
    (net (code "152") (name "unconnected-(U$1-PadP$114)") (class "Default")
      (node (ref "U$1") (pin "P$114") (pinfunction "P$114_P$114") (pintype "bidirectional"))
    )
    (net (code "153") (name "unconnected-(U$1-PadP$115)") (class "Default")
      (node (ref "U$1") (pin "P$115") (pinfunction "P$115_P$115") (pintype "bidirectional"))
    )
    (net (code "154") (name "unconnected-(U$1-PadP$116)") (class "Default")
      (node (ref "U$1") (pin "P$116") (pinfunction "P$116_P$116") (pintype "bidirectional"))
    )
    (net (code "155") (name "unconnected-(U$1-PadP$117)") (class "Default")
      (node (ref "U$1") (pin "P$117") (pinfunction "P$117_P$117") (pintype "bidirectional"))
    )
    (net (code "156") (name "unconnected-(U$1-PadP$119)") (class "Default")
      (node (ref "U$1") (pin "P$119") (pinfunction "P$119_P$119") (pintype "bidirectional"))
    )
    (net (code "157") (name "unconnected-(U$1-PadP$120)") (class "Default")
      (node (ref "U$1") (pin "P$120") (pinfunction "P$120_P$120") (pintype "bidirectional"))
    )
    (net (code "158") (name "unconnected-(U$1-SD-CLK-PadP$106)") (class "Default")
      (node (ref "U$1") (pin "P$106") (pinfunction "SD-CLK_P$106") (pintype "bidirectional"))
    )
    (net (code "159") (name "unconnected-(U$1-SD-CMD-PadP$105)") (class "Default")
      (node (ref "U$1") (pin "P$105") (pinfunction "SD-CMD_P$105") (pintype "bidirectional"))
    )
    (net (code "160") (name "unconnected-(U$1-SD-D0-PadP$104)") (class "Default")
      (node (ref "U$1") (pin "P$104") (pinfunction "SD-D0_P$104") (pintype "bidirectional"))
    )
    (net (code "161") (name "unconnected-(U$1-SD-D1-PadP$103)") (class "Default")
      (node (ref "U$1") (pin "P$103") (pinfunction "SD-D1_P$103") (pintype "bidirectional"))
    )
    (net (code "162") (name "unconnected-(U$1-SD-D2-PadP$102)") (class "Default")
      (node (ref "U$1") (pin "P$102") (pinfunction "SD-D2_P$102") (pintype "bidirectional"))
    )
    (net (code "163") (name "unconnected-(U$1-SD-D3-PadP$101)") (class "Default")
      (node (ref "U$1") (pin "P$101") (pinfunction "SD-D3_P$101") (pintype "bidirectional"))
    )
    (net (code "164") (name "unconnected-(U$1-SPI0-CLK-PadP$62)") (class "Default")
      (node (ref "U$1") (pin "P$62") (pinfunction "SPI0-CLK_P$62") (pintype "bidirectional"))
    )
    (net (code "165") (name "unconnected-(U$1-SPI0-CSN0-PadP$59)") (class "Default")
      (node (ref "U$1") (pin "P$59") (pinfunction "SPI0-CSN0_P$59") (pintype "bidirectional"))
    )
    (net (code "166") (name "unconnected-(U$1-SPI0-CSN1-PadP$63)") (class "Default")
      (node (ref "U$1") (pin "P$63") (pinfunction "SPI0-CSN1_P$63") (pintype "bidirectional"))
    )
    (net (code "167") (name "unconnected-(U$1-SPI0-MISO-PadP$60)") (class "Default")
      (node (ref "U$1") (pin "P$60") (pinfunction "SPI0-MISO_P$60") (pintype "bidirectional"))
    )
    (net (code "168") (name "unconnected-(U$1-SPI0-MOSI-PadP$61)") (class "Default")
      (node (ref "U$1") (pin "P$61") (pinfunction "SPI0-MOSI_P$61") (pintype "bidirectional"))
    )
    (net (code "169") (name "unconnected-(U$1-SPI1-CLK-PadP$70)") (class "Default")
      (node (ref "U$1") (pin "P$70") (pinfunction "SPI1-CLK_P$70") (pintype "bidirectional"))
    )
    (net (code "170") (name "unconnected-(U$1-SPI1-CSN0-PadP$64)") (class "Default")
      (node (ref "U$1") (pin "P$64") (pinfunction "SPI1-CSN0_P$64") (pintype "bidirectional"))
    )
    (net (code "171") (name "unconnected-(U$1-SPI1-MISO-PadP$68)") (class "Default")
      (node (ref "U$1") (pin "P$68") (pinfunction "SPI1-MISO_P$68") (pintype "bidirectional"))
    )
    (net (code "172") (name "unconnected-(U$1-SPI1-MOSI-PadP$69)") (class "Default")
      (node (ref "U$1") (pin "P$69") (pinfunction "SPI1-MOSI_P$69") (pintype "bidirectional"))
    )
    (net (code "173") (name "unconnected-(U$1-SPI2-CLK-PadP$18)") (class "Default")
      (node (ref "U$1") (pin "P$18") (pinfunction "SPI2-CLK_P$18") (pintype "bidirectional"))
    )
    (net (code "174") (name "unconnected-(U$1-SPI2-CSN-PadP$17)") (class "Default")
      (node (ref "U$1") (pin "P$17") (pinfunction "SPI2-CSN_P$17") (pintype "bidirectional"))
    )
    (net (code "175") (name "unconnected-(U$1-SPI2-MISO-PadP$15)") (class "Default")
      (node (ref "U$1") (pin "P$15") (pinfunction "SPI2-MISO_P$15") (pintype "bidirectional"))
    )
    (net (code "176") (name "unconnected-(U$1-SPI2-MOSI-PadP$16)") (class "Default")
      (node (ref "U$1") (pin "P$16") (pinfunction "SPI2-MOSI_P$16") (pintype "bidirectional"))
    )
    (net (code "177") (name "unconnected-(U$1-UART0-RX-PadP$56)") (class "Default")
      (node (ref "U$1") (pin "P$56") (pinfunction "UART0-RX_P$56") (pintype "bidirectional"))
    )
    (net (code "178") (name "unconnected-(U$1-UART0-TX-PadP$57)") (class "Default")
      (node (ref "U$1") (pin "P$57") (pinfunction "UART0-TX_P$57") (pintype "bidirectional"))
    )
    (net (code "179") (name "unconnected-(U$1-UART5-CTSN-PadP$95)") (class "Default")
      (node (ref "U$1") (pin "P$95") (pinfunction "UART5-CTSN_P$95") (pintype "bidirectional"))
    )
    (net (code "180") (name "unconnected-(U$1-UART5-RTSN-PadP$92)") (class "Default")
      (node (ref "U$1") (pin "P$92") (pinfunction "UART5-RTSN_P$92") (pintype "bidirectional"))
    )
    (net (code "181") (name "unconnected-(U$1-UART5-RX-PadP$94)") (class "Default")
      (node (ref "U$1") (pin "P$94") (pinfunction "UART5-RX_P$94") (pintype "bidirectional"))
    )
    (net (code "182") (name "unconnected-(U$1-UART5-TX-PadP$93)") (class "Default")
      (node (ref "U$1") (pin "P$93") (pinfunction "UART5-TX_P$93") (pintype "bidirectional"))
    )
    (net (code "183") (name "unconnected-(U$1-USB0-ID-PadP$112)") (class "Default")
      (node (ref "U$1") (pin "P$112") (pinfunction "USB0-ID_P$112") (pintype "bidirectional"))
    )
    (net (code "184") (name "unconnected-(U$1-USB0-VBUSDET-PadP$113)") (class "Default")
      (node (ref "U$1") (pin "P$113") (pinfunction "USB0-VBUSDET_P$113") (pintype "bidirectional"))
    )
    (net (code "185") (name "unconnected-(U$1-USB1-DN-PadP$111)") (class "Default")
      (node (ref "U$1") (pin "P$111") (pinfunction "USB1-DN_P$111") (pintype "bidirectional"))
    )
    (net (code "186") (name "unconnected-(U$1-USB1-DP-PadP$110)") (class "Default")
      (node (ref "U$1") (pin "P$110") (pinfunction "USB1-DP_P$110") (pintype "bidirectional"))
    )
    (net (code "187") (name "unconnected-(U2-TS-Pad47)") (class "Default")
      (node (ref "U2") (pin "47") (pinfunction "TS_47") (pintype "input"))
    )
  )
)
